# automation-v3.net
KiCad netlist of a schematic drawn in EAGLE
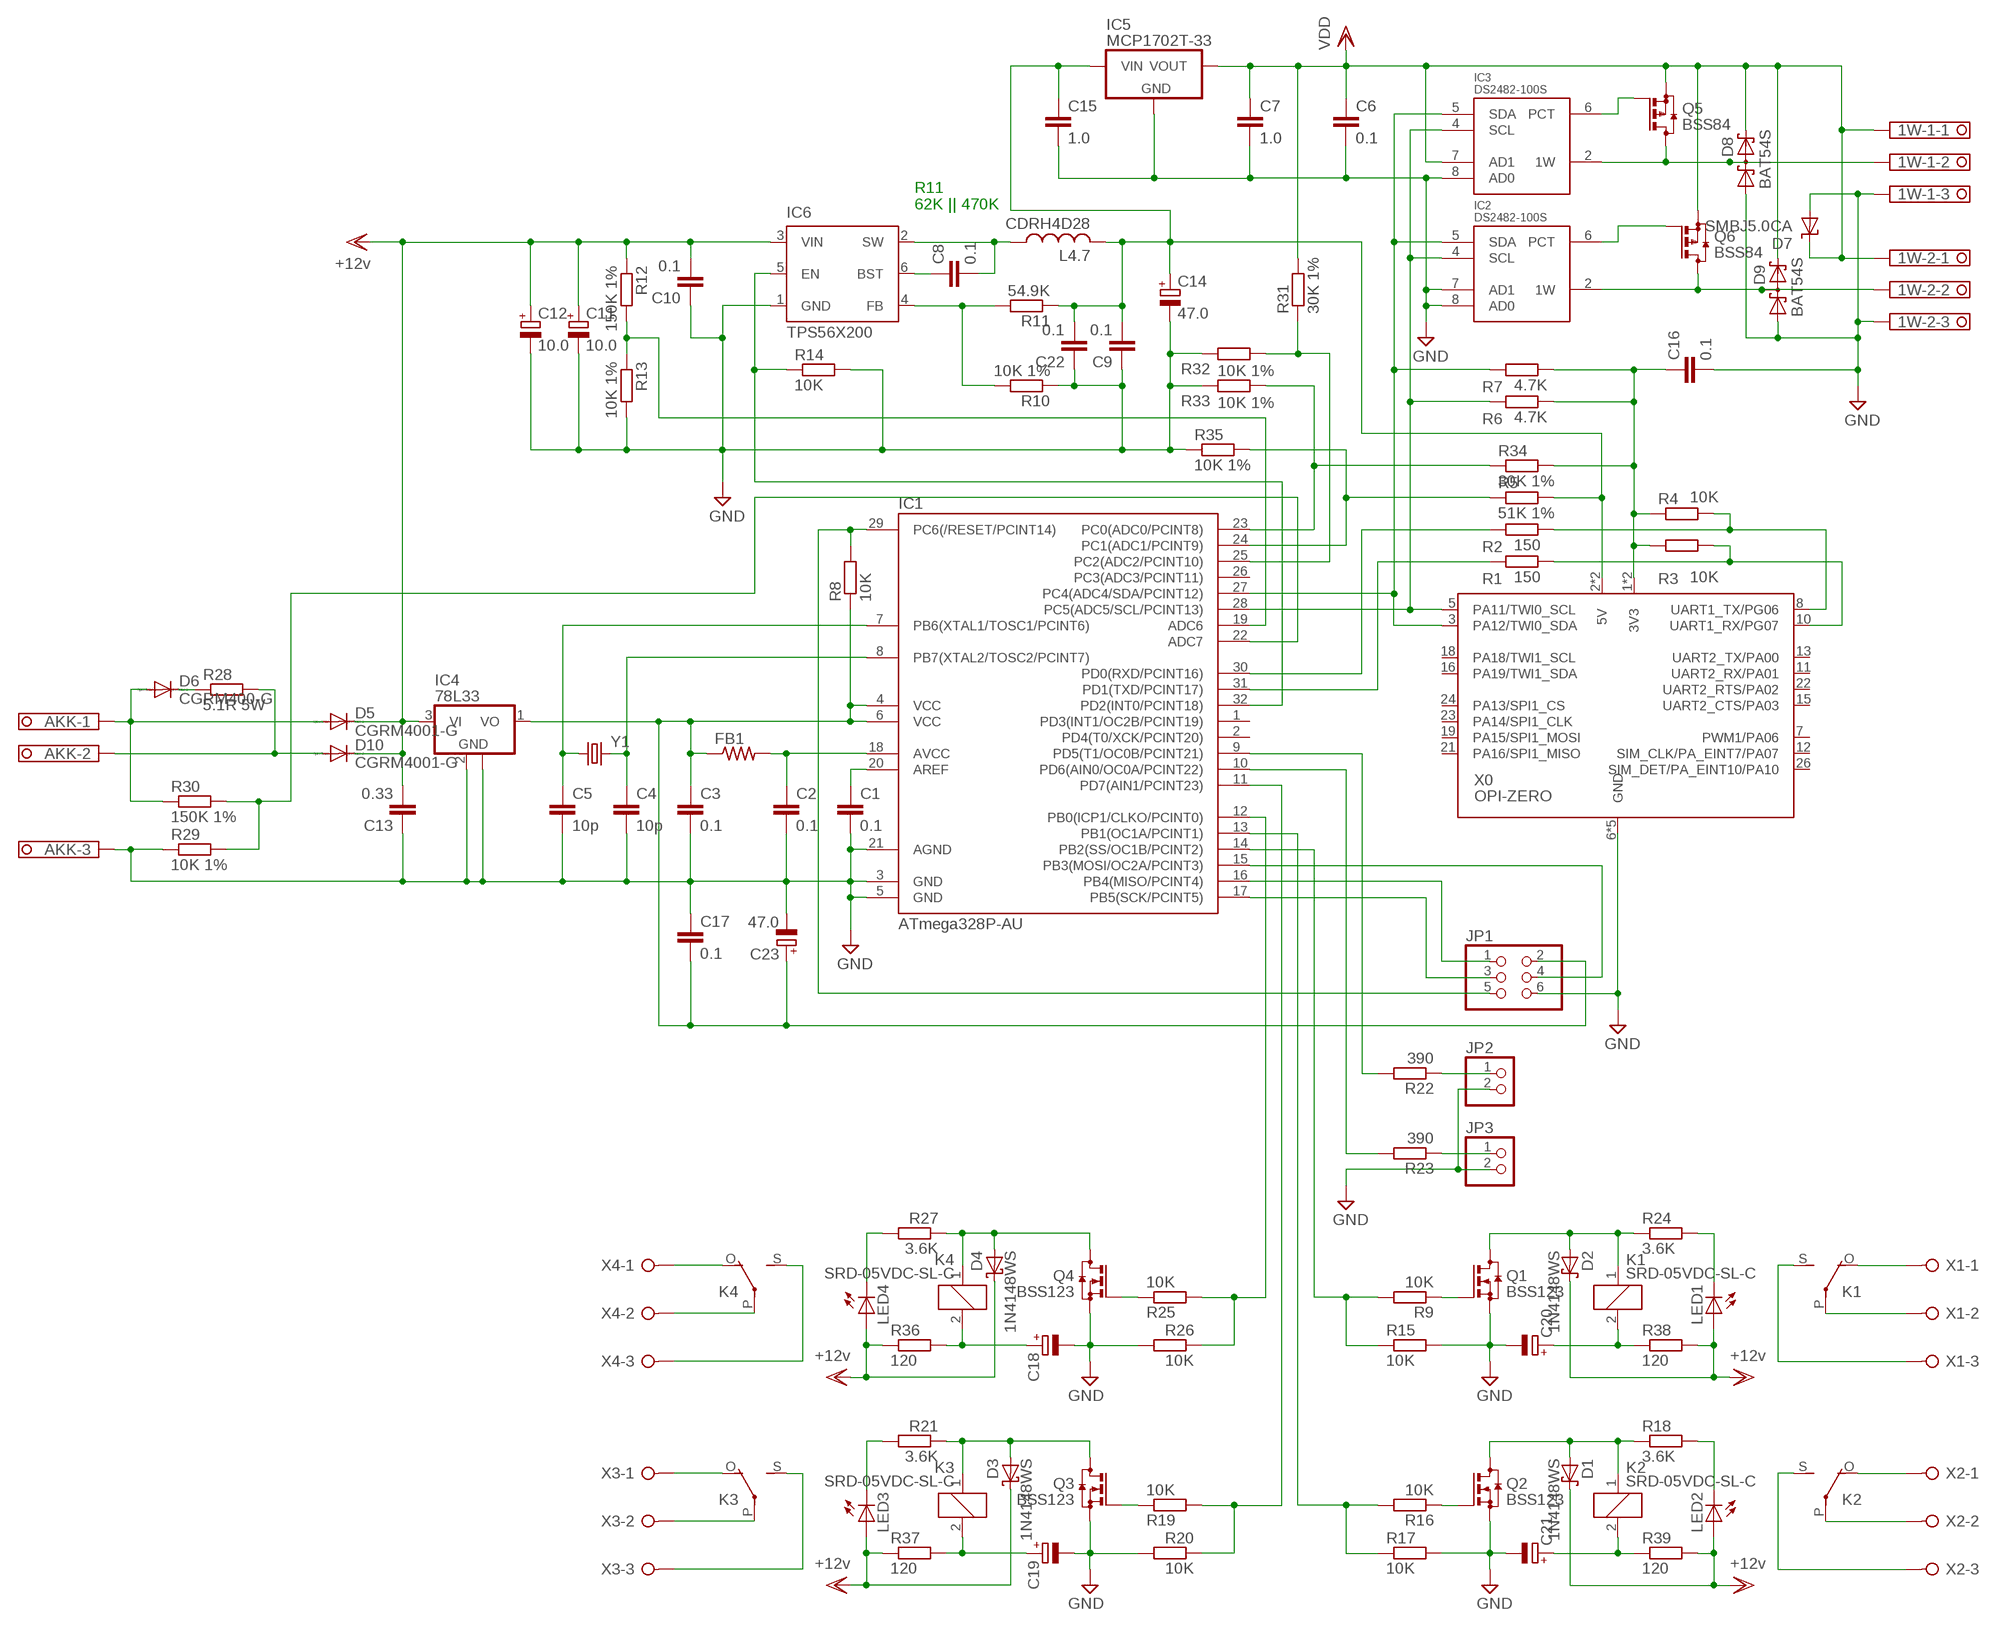
[diagram p0: schematic, sheet 1]

(export (version "E")
  (design (tool "Eeschema 10.0.6"))
  (components
    (comp (ref "1W-1")
      (value "1751251")
      (footprint "eagle-import:1751251")
      (libsource (lib "eagle-import") (part "1751251"))
    )
    (comp (ref "1W-2")
      (value "1751251")
      (footprint "eagle-import:1751251")
      (libsource (lib "eagle-import") (part "1751251"))
    )
    (comp (ref "AKK")
      (value "1751251")
      (footprint "eagle-import:1751251")
      (libsource (lib "eagle-import") (part "1751251"))
    )
    (comp (ref "C1")
      (value "0.1")
      (footprint "eagle-import:C0603")
      (libsource (lib "eagle-import") (part "C-EUC0603"))
    )
    (comp (ref "C2")
      (value "0.1")
      (footprint "eagle-import:C0603")
      (libsource (lib "eagle-import") (part "C-EUC0603"))
    )
    (comp (ref "C3")
      (value "0.1")
      (footprint "eagle-import:C0603")
      (libsource (lib "eagle-import") (part "C-EUC0603"))
    )
    (comp (ref "C4")
      (value "10p")
      (footprint "eagle-import:C0603")
      (libsource (lib "eagle-import") (part "C-EUC0603"))
    )
    (comp (ref "C5")
      (value "10p")
      (footprint "eagle-import:C0603")
      (libsource (lib "eagle-import") (part "C-EUC0603"))
    )
    (comp (ref "C6")
      (value "0.1")
      (footprint "eagle-import:C0603")
      (libsource (lib "eagle-import") (part "C-EUC0603"))
    )
    (comp (ref "C7")
      (value "1.0")
      (footprint "eagle-import:C0805")
      (libsource (lib "eagle-import") (part "C-EUC0805"))
    )
    (comp (ref "C8")
      (value "0.1")
      (footprint "eagle-import:C0805")
      (libsource (lib "eagle-import") (part "C-EUC0805"))
    )
    (comp (ref "C9")
      (value "0.1")
      (footprint "eagle-import:C0805")
      (libsource (lib "eagle-import") (part "C-EUC0805"))
    )
    (comp (ref "C10")
      (value "0.1")
      (footprint "eagle-import:C0805")
      (libsource (lib "eagle-import") (part "C-EUC0805"))
    )
    (comp (ref "C11")
      (value "10.0")
      (footprint "eagle-import:C_6032-28R")
      (libsource (lib "eagle-import") (part "CPOL-EUC/6032-28R"))
    )
    (comp (ref "C12")
      (value "10.0")
      (footprint "eagle-import:C_6032-28R")
      (libsource (lib "eagle-import") (part "CPOL-EUC/6032-28R"))
    )
    (comp (ref "C13")
      (value "0.33")
      (footprint "eagle-import:C0805")
      (libsource (lib "eagle-import") (part "C-EUC0805"))
    )
    (comp (ref "C14")
      (value "47.0")
      (footprint "eagle-import:B_3528-21R")
      (libsource (lib "eagle-import") (part "CPOL-EUB/3528-21R"))
    )
    (comp (ref "C15")
      (value "1.0")
      (footprint "eagle-import:C0805")
      (libsource (lib "eagle-import") (part "C-EUC0805"))
    )
    (comp (ref "C16")
      (value "0.1")
      (footprint "eagle-import:C0603")
      (libsource (lib "eagle-import") (part "C-EUC0603"))
    )
    (comp (ref "C17")
      (value "0.1")
      (footprint "eagle-import:C0603")
      (libsource (lib "eagle-import") (part "C-EUC0603"))
    )
    (comp (ref "C18")
      (value "CPOL-EUE5-10.5")
      (footprint "eagle-import:E5-10,5")
      (libsource (lib "eagle-import") (part "CPOL-EUE5-10.5"))
    )
    (comp (ref "C19")
      (value "CPOL-EUE5-10.5")
      (footprint "eagle-import:E5-10,5")
      (libsource (lib "eagle-import") (part "CPOL-EUE5-10.5"))
    )
    (comp (ref "C20")
      (value "CPOL-EUE5-10.5")
      (footprint "eagle-import:E5-10,5")
      (libsource (lib "eagle-import") (part "CPOL-EUE5-10.5"))
    )
    (comp (ref "C21")
      (value "CPOL-EUE5-10.5")
      (footprint "eagle-import:E5-10,5")
      (libsource (lib "eagle-import") (part "CPOL-EUE5-10.5"))
    )
    (comp (ref "C22")
      (value "0.1")
      (footprint "eagle-import:C0805")
      (libsource (lib "eagle-import") (part "C-EUC0805"))
    )
    (comp (ref "C23")
      (value "47.0")
      (footprint "eagle-import:B_3528-21R")
      (libsource (lib "eagle-import") (part "CPOL-EUB/3528-21R"))
    )
    (comp (ref "D1")
      (value "1N4148WS")
      (footprint "eagle-import:SOD323_ST")
      (libsource (lib "eagle-import") (part "BAT60J"))
    )
    (comp (ref "D2")
      (value "1N4148WS")
      (footprint "eagle-import:SOD323_ST")
      (libsource (lib "eagle-import") (part "BAT60J"))
    )
    (comp (ref "D3")
      (value "1N4148WS")
      (footprint "eagle-import:SOD323_ST")
      (libsource (lib "eagle-import") (part "BAT60J"))
    )
    (comp (ref "D4")
      (value "1N4148WS")
      (footprint "eagle-import:SOD323_ST")
      (libsource (lib "eagle-import") (part "BAT60J"))
    )
    (comp (ref "D5")
      (value "CGRM4001-G")
      (footprint "eagle-import:SOD-123_MINI-SMA")
      (libsource (lib "eagle-import") (part "CGRM400-G1"))
    )
    (comp (ref "D6")
      (value "CGRM400-G")
      (footprint "eagle-import:SOD-123_MINI-SMA")
      (libsource (lib "eagle-import") (part "CGRM400-G1"))
    )
    (comp (ref "D7")
      (value "SMBJ5.0CA")
      (footprint "eagle-import:SMBJ")
      (libsource (lib "eagle-import") (part "SUPPRESSOR-SMBJ"))
    )
    (comp (ref "D8")
      (value "BAT54S")
      (footprint "eagle-import:SOT23")
      (libsource (lib "eagle-import") (part "BAT54S"))
    )
    (comp (ref "D9")
      (value "BAT54S")
      (footprint "eagle-import:SOT23")
      (libsource (lib "eagle-import") (part "BAT54S"))
    )
    (comp (ref "D10")
      (value "CGRM4001-G")
      (footprint "eagle-import:SOD-123_MINI-SMA")
      (libsource (lib "eagle-import") (part "CGRM400-G1"))
    )
    (comp (ref "FB1")
      (value "R-US_R0805")
      (footprint "eagle-import:R0805")
      (libsource (lib "eagle-import") (part "R-US_R0805"))
    )
    (comp (ref "IC1")
      (value "ATmega328P-AU")
      (footprint "eagle-import:TQFP32-08")
      (libsource (lib "eagle-import") (part "MEGA48/88/168-AU"))
    )
    (comp (ref "IC2")
      (value "DS2482-100S")
      (footprint "eagle-import:SO08")
      (libsource (lib "eagle-import") (part "DS2482-100S"))
    )
    (comp (ref "IC3")
      (value "DS2482-100S")
      (footprint "eagle-import:SO08")
      (libsource (lib "eagle-import") (part "DS2482-100S"))
    )
    (comp (ref "IC4")
      (value "78L33")
      (footprint "eagle-import:SOT89")
      (libsource (lib "eagle-import") (part "78LF05"))
    )
    (comp (ref "IC5")
      (value "MCP1702T-33")
      (footprint "eagle-import:SOT23-3-ROTATED")
      (libsource (lib "eagle-import") (part "MCP1702SOT23"))
    )
    (comp (ref "IC6")
      (value "TPS56X200")
      (footprint "eagle-import:TSOT23-6_DDC")
      (libsource (lib "eagle-import") (part "TPS56X200"))
    )
    (comp (ref "JP1")
      (value "PINHD-2X3")
      (footprint "eagle-import:2X03")
      (libsource (lib "eagle-import") (part "PINHD-2X3"))
    )
    (comp (ref "JP2")
      (value "PINHD-1X2")
      (footprint "eagle-import:1X02")
      (libsource (lib "eagle-import") (part "PINHD-1X2"))
    )
    (comp (ref "JP3")
      (value "PINHD-1X2")
      (footprint "eagle-import:1X02")
      (libsource (lib "eagle-import") (part "PINHD-1X2"))
    )
    (comp (ref "K1")
      (value "SRD-05VDC-SL-C")
      (footprint "eagle-import:NRP18")
      (libsource (lib "eagle-import") (part "ZF112S"))
    )
    (comp (ref "K2")
      (value "SRD-05VDC-SL-C")
      (footprint "eagle-import:NRP18")
      (libsource (lib "eagle-import") (part "ZF112S"))
    )
    (comp (ref "K3")
      (value "SRD-05VDC-SL-C")
      (footprint "eagle-import:NRP18")
      (libsource (lib "eagle-import") (part "ZF112S"))
    )
    (comp (ref "K4")
      (value "SRD-05VDC-SL-C")
      (footprint "eagle-import:NRP18")
      (libsource (lib "eagle-import") (part "ZF112S"))
    )
    (comp (ref "L4.7")
      (value "CDRH4D28")
      (footprint "eagle-import:CDRH4D28")
      (libsource (lib "eagle-import") (part "CDRH4D28"))
    )
    (comp (ref "LED1")
      (value "LEDSML0805")
      (footprint "eagle-import:SML0805")
      (libsource (lib "eagle-import") (part "LEDSML0805"))
    )
    (comp (ref "LED2")
      (value "LEDSML0805")
      (footprint "eagle-import:SML0805")
      (libsource (lib "eagle-import") (part "LEDSML0805"))
    )
    (comp (ref "LED3")
      (value "LEDSML0805")
      (footprint "eagle-import:SML0805")
      (libsource (lib "eagle-import") (part "LEDSML0805"))
    )
    (comp (ref "LED4")
      (value "LEDSML0805")
      (footprint "eagle-import:SML0805")
      (libsource (lib "eagle-import") (part "LEDSML0805"))
    )
    (comp (ref "Q1")
      (value "BSS123")
      (footprint "eagle-import:SOT23")
      (libsource (lib "eagle-import") (part "BSS123"))
    )
    (comp (ref "Q2")
      (value "BSS123")
      (footprint "eagle-import:SOT23")
      (libsource (lib "eagle-import") (part "BSS123"))
    )
    (comp (ref "Q3")
      (value "BSS123")
      (footprint "eagle-import:SOT23")
      (libsource (lib "eagle-import") (part "BSS123"))
    )
    (comp (ref "Q4")
      (value "BSS123")
      (footprint "eagle-import:SOT23")
      (libsource (lib "eagle-import") (part "BSS123"))
    )
    (comp (ref "Q5")
      (value "BSS84")
      (footprint "eagle-import:SOT23")
      (libsource (lib "eagle-import") (part "BSS84"))
    )
    (comp (ref "Q6")
      (value "BSS84")
      (footprint "eagle-import:SOT23")
      (libsource (lib "eagle-import") (part "BSS84"))
    )
    (comp (ref "R1")
      (value "150")
      (footprint "eagle-import:R0603")
      (libsource (lib "eagle-import") (part "R-EU_R0603"))
    )
    (comp (ref "R2")
      (value "150")
      (footprint "eagle-import:R0603")
      (libsource (lib "eagle-import") (part "R-EU_R0603"))
    )
    (comp (ref "R3")
      (value "10K")
      (footprint "eagle-import:R0603")
      (libsource (lib "eagle-import") (part "R-EU_R0603"))
    )
    (comp (ref "R4")
      (value "10K")
      (footprint "eagle-import:R0603")
      (libsource (lib "eagle-import") (part "R-EU_R0603"))
    )
    (comp (ref "R5")
      (value "51K 1%")
      (footprint "eagle-import:R0603")
      (libsource (lib "eagle-import") (part "R-EU_R0603"))
    )
    (comp (ref "R6")
      (value "4.7K")
      (footprint "eagle-import:R0603")
      (libsource (lib "eagle-import") (part "R-EU_R0603"))
    )
    (comp (ref "R7")
      (value "4.7K")
      (footprint "eagle-import:R0603")
      (libsource (lib "eagle-import") (part "R-EU_R0603"))
    )
    (comp (ref "R8")
      (value "10K")
      (footprint "eagle-import:R0603")
      (libsource (lib "eagle-import") (part "R-EU_R0603"))
    )
    (comp (ref "R9")
      (value "10K")
      (footprint "eagle-import:R0603")
      (libsource (lib "eagle-import") (part "R-EU_R0603"))
    )
    (comp (ref "R10")
      (value "10K 1%")
      (footprint "eagle-import:R0603")
      (libsource (lib "eagle-import") (part "R-EU_R0603"))
    )
    (comp (ref "R11")
      (value "54.9K")
      (footprint "eagle-import:R0603")
      (libsource (lib "eagle-import") (part "R-EU_R0603"))
    )
    (comp (ref "R12")
      (value "150K 1%")
      (footprint "eagle-import:R0603")
      (libsource (lib "eagle-import") (part "R-EU_R0603"))
    )
    (comp (ref "R13")
      (value "10K 1%")
      (footprint "eagle-import:R0603")
      (libsource (lib "eagle-import") (part "R-EU_R0603"))
    )
    (comp (ref "R14")
      (value "10K")
      (footprint "eagle-import:R0603")
      (libsource (lib "eagle-import") (part "R-EU_R0603"))
    )
    (comp (ref "R15")
      (value "10K")
      (footprint "eagle-import:R0603")
      (libsource (lib "eagle-import") (part "R-EU_R0603"))
    )
    (comp (ref "R16")
      (value "10K")
      (footprint "eagle-import:R0603")
      (libsource (lib "eagle-import") (part "R-EU_R0603"))
    )
    (comp (ref "R17")
      (value "10K")
      (footprint "eagle-import:R0603")
      (libsource (lib "eagle-import") (part "R-EU_R0603"))
    )
    (comp (ref "R18")
      (value "3.6K")
      (footprint "eagle-import:R0603")
      (libsource (lib "eagle-import") (part "R-EU_R0603"))
    )
    (comp (ref "R19")
      (value "10K")
      (footprint "eagle-import:R0603")
      (libsource (lib "eagle-import") (part "R-EU_R0603"))
    )
    (comp (ref "R20")
      (value "10K")
      (footprint "eagle-import:R0603")
      (libsource (lib "eagle-import") (part "R-EU_R0603"))
    )
    (comp (ref "R21")
      (value "3.6K")
      (footprint "eagle-import:R0603")
      (libsource (lib "eagle-import") (part "R-EU_R0603"))
    )
    (comp (ref "R22")
      (value "390")
      (footprint "eagle-import:R0603")
      (libsource (lib "eagle-import") (part "R-EU_R0603"))
    )
    (comp (ref "R23")
      (value "390")
      (footprint "eagle-import:R0603")
      (libsource (lib "eagle-import") (part "R-EU_R0603"))
    )
    (comp (ref "R24")
      (value "3.6K")
      (footprint "eagle-import:R0603")
      (libsource (lib "eagle-import") (part "R-EU_R0603"))
    )
    (comp (ref "R25")
      (value "10K")
      (footprint "eagle-import:R0603")
      (libsource (lib "eagle-import") (part "R-EU_R0603"))
    )
    (comp (ref "R26")
      (value "10K")
      (footprint "eagle-import:R0603")
      (libsource (lib "eagle-import") (part "R-EU_R0603"))
    )
    (comp (ref "R27")
      (value "3.6K")
      (footprint "eagle-import:R0603")
      (libsource (lib "eagle-import") (part "R-EU_R0603"))
    )
    (comp (ref "R28")
      (value "5.1R 5W")
      (footprint "eagle-import:VTA55")
      (libsource (lib "eagle-import") (part "R-EU_VTA55"))
    )
    (comp (ref "R29")
      (value "10K 1%")
      (footprint "eagle-import:R0603")
      (libsource (lib "eagle-import") (part "R-EU_R0603"))
    )
    (comp (ref "R30")
      (value "150K 1%")
      (footprint "eagle-import:R0603")
      (libsource (lib "eagle-import") (part "R-EU_R0603"))
    )
    (comp (ref "R31")
      (value "30K 1%")
      (footprint "eagle-import:R0603")
      (libsource (lib "eagle-import") (part "R-EU_R0603"))
    )
    (comp (ref "R32")
      (value "10K 1%")
      (footprint "eagle-import:R0603")
      (libsource (lib "eagle-import") (part "R-EU_R0603"))
    )
    (comp (ref "R33")
      (value "10K 1%")
      (footprint "eagle-import:R0603")
      (libsource (lib "eagle-import") (part "R-EU_R0603"))
    )
    (comp (ref "R34")
      (value "30K 1%")
      (footprint "eagle-import:R0603")
      (libsource (lib "eagle-import") (part "R-EU_R0603"))
    )
    (comp (ref "R35")
      (value "10K 1%")
      (footprint "eagle-import:R0603")
      (libsource (lib "eagle-import") (part "R-EU_R0603"))
    )
    (comp (ref "R36")
      (value "120")
      (footprint "eagle-import:M1206")
      (libsource (lib "eagle-import") (part "R-EU_M1206"))
    )
    (comp (ref "R37")
      (value "120")
      (footprint "eagle-import:M1206")
      (libsource (lib "eagle-import") (part "R-EU_M1206"))
    )
    (comp (ref "R38")
      (value "120")
      (footprint "eagle-import:M1206")
      (libsource (lib "eagle-import") (part "R-EU_M1206"))
    )
    (comp (ref "R39")
      (value "120")
      (footprint "eagle-import:M1206")
      (libsource (lib "eagle-import") (part "R-EU_M1206"))
    )
    (comp (ref "X0")
      (value "OPI-ZERO")
      (footprint "eagle-import:OPI0")
      (libsource (lib "eagle-import") (part "OPI-ZERO"))
    )
    (comp (ref "X1")
      (value "W237-03P")
      (footprint "eagle-import:W237-133")
      (libsource (lib "eagle-import") (part "W237-03P"))
    )
    (comp (ref "X2")
      (value "W237-03P")
      (footprint "eagle-import:W237-133")
      (libsource (lib "eagle-import") (part "W237-03P"))
    )
    (comp (ref "X3")
      (value "W237-03P")
      (footprint "eagle-import:W237-133")
      (libsource (lib "eagle-import") (part "W237-03P"))
    )
    (comp (ref "X4")
      (value "W237-03P")
      (footprint "eagle-import:W237-133")
      (libsource (lib "eagle-import") (part "W237-03P"))
    )
    (comp (ref "Y1")
      (value "CRYSTALHC49US")
      (footprint "eagle-import:HC49US")
      (libsource (lib "eagle-import") (part "CRYSTALHC49US"))
    )
  )
  (nets
    (net (code "1") (name "+12v") (class "Default")
      (node (ref "C10") (pin "2") (pinfunction "2_2") (pintype "passive"))
      (node (ref "C11") (pin "+") (pinfunction "+_+") (pintype "passive"))
      (node (ref "C12") (pin "+") (pinfunction "+_+") (pintype "passive"))
      (node (ref "C13") (pin "2") (pinfunction "2_2") (pintype "passive"))
      (node (ref "D1") (pin "C") (pinfunction "C_C") (pintype "passive"))
      (node (ref "D10") (pin "C") (pinfunction "C_C") (pintype "passive"))
      (node (ref "D2") (pin "C") (pinfunction "C_C") (pintype "passive"))
      (node (ref "D3") (pin "C") (pinfunction "C_C") (pintype "passive"))
      (node (ref "D4") (pin "C") (pinfunction "C_C") (pintype "passive"))
      (node (ref "D5") (pin "C") (pinfunction "C_C") (pintype "passive"))
      (node (ref "IC4") (pin "3") (pinfunction "VI_3") (pintype "input"))
      (node (ref "IC6") (pin "3") (pinfunction "VIN_3") (pintype "input"))
      (node (ref "LED1") (pin "A") (pinfunction "A_A") (pintype "passive"))
      (node (ref "LED2") (pin "A") (pinfunction "A_A") (pintype "passive"))
      (node (ref "LED3") (pin "A") (pinfunction "A_A") (pintype "passive"))
      (node (ref "LED4") (pin "A") (pinfunction "A_A") (pintype "passive"))
      (node (ref "R12") (pin "1") (pinfunction "1_1") (pintype "passive"))
      (node (ref "R36") (pin "1") (pinfunction "1_1") (pintype "passive"))
      (node (ref "R37") (pin "1") (pinfunction "1_1") (pintype "passive"))
      (node (ref "R38") (pin "2") (pinfunction "2_2") (pintype "passive"))
      (node (ref "R39") (pin "2") (pinfunction "2_2") (pintype "passive"))
    )
    (net (code "2") (name "GND") (class "Default")
      (node (ref "1W-1") (pin "3") (pinfunction "K_3") (pintype "passive"))
      (node (ref "1W-2") (pin "3") (pinfunction "K_3") (pintype "passive"))
      (node (ref "AKK") (pin "3") (pinfunction "K_3") (pintype "passive"))
      (node (ref "C1") (pin "2") (pinfunction "2_2") (pintype "passive"))
      (node (ref "C10") (pin "1") (pinfunction "1_1") (pintype "passive"))
      (node (ref "C11") (pin "-") (pinfunction "-_-") (pintype "passive"))
      (node (ref "C12") (pin "-") (pinfunction "-_-") (pintype "passive"))
      (node (ref "C13") (pin "1") (pinfunction "1_1") (pintype "passive"))
      (node (ref "C14") (pin "-") (pinfunction "-_-") (pintype "passive"))
      (node (ref "C15") (pin "2") (pinfunction "2_2") (pintype "passive"))
      (node (ref "C16") (pin "2") (pinfunction "2_2") (pintype "passive"))
      (node (ref "C17") (pin "1") (pinfunction "1_1") (pintype "passive"))
      (node (ref "C18") (pin "-") (pinfunction "-_-") (pintype "passive"))
      (node (ref "C19") (pin "-") (pinfunction "-_-") (pintype "passive"))
      (node (ref "C2") (pin "2") (pinfunction "2_2") (pintype "passive"))
      (node (ref "C20") (pin "-") (pinfunction "-_-") (pintype "passive"))
      (node (ref "C21") (pin "-") (pinfunction "-_-") (pintype "passive"))
      (node (ref "C22") (pin "1") (pinfunction "1_1") (pintype "passive"))
      (node (ref "C23") (pin "-") (pinfunction "-_-") (pintype "passive"))
      (node (ref "C3") (pin "2") (pinfunction "2_2") (pintype "passive"))
      (node (ref "C4") (pin "2") (pinfunction "2_2") (pintype "passive"))
      (node (ref "C5") (pin "2") (pinfunction "2_2") (pintype "passive"))
      (node (ref "C6") (pin "2") (pinfunction "2_2") (pintype "passive"))
      (node (ref "C7") (pin "2") (pinfunction "2_2") (pintype "passive"))
      (node (ref "C9") (pin "1") (pinfunction "1_1") (pintype "passive"))
      (node (ref "D7") (pin "A") (pinfunction "A_A") (pintype "passive"))
      (node (ref "D8") (pin "1") (pinfunction "A1_1") (pintype "passive"))
      (node (ref "D9") (pin "1") (pinfunction "A1_1") (pintype "passive"))
      (node (ref "IC1") (pin "21") (pinfunction "AGND_21") (pintype "power_in"))
      (node (ref "IC1") (pin "3") (pinfunction "GND_3") (pintype "power_in"))
      (node (ref "IC1") (pin "5") (pinfunction "GND_5") (pintype "power_in"))
      (node (ref "IC2") (pin "7") (pinfunction "AD1_7") (pintype "input"))
      (node (ref "IC2") (pin "8") (pinfunction "AD0_8") (pintype "input"))
      (node (ref "IC3") (pin "8") (pinfunction "AD0_8") (pintype "input"))
      (node (ref "IC4") (pin "2") (pinfunction "GND_2") (pintype "passive"))
      (node (ref "IC4") (pin "2@1") (pinfunction "GND_2@1") (pintype "passive"))
      (node (ref "IC5") (pin "1") (pinfunction "GND_1") (pintype "passive"))
      (node (ref "IC6") (pin "1") (pinfunction "GND_1") (pintype "power_in"))
      (node (ref "JP1") (pin "6") (pinfunction "6_6") (pintype "passive"))
      (node (ref "JP2") (pin "2") (pinfunction "2_2") (pintype "passive"))
      (node (ref "JP3") (pin "2") (pinfunction "2_2") (pintype "passive"))
      (node (ref "Q1") (pin "2") (pinfunction "S_2") (pintype "passive"))
      (node (ref "Q2") (pin "2") (pinfunction "S_2") (pintype "passive"))
      (node (ref "Q3") (pin "2") (pinfunction "S_2") (pintype "passive"))
      (node (ref "Q4") (pin "2") (pinfunction "S_2") (pintype "passive"))
      (node (ref "R10") (pin "1") (pinfunction "1_1") (pintype "passive"))
      (node (ref "R13") (pin "2") (pinfunction "2_2") (pintype "passive"))
      (node (ref "R14") (pin "2") (pinfunction "2_2") (pintype "passive"))
      (node (ref "R15") (pin "2") (pinfunction "2_2") (pintype "passive"))
      (node (ref "R17") (pin "2") (pinfunction "2_2") (pintype "passive"))
      (node (ref "R20") (pin "2") (pinfunction "2_2") (pintype "passive"))
      (node (ref "R26") (pin "2") (pinfunction "2_2") (pintype "passive"))
      (node (ref "R29") (pin "1") (pinfunction "1_1") (pintype "passive"))
      (node (ref "R32") (pin "2") (pinfunction "2_2") (pintype "passive"))
      (node (ref "R33") (pin "2") (pinfunction "2_2") (pintype "passive"))
      (node (ref "R35") (pin "1") (pinfunction "1_1") (pintype "passive"))
      (node (ref "X0") (pin "14") (pinfunction "GND_14") (pintype "power_in"))
      (node (ref "X0") (pin "20") (pinfunction "GND_20") (pintype "power_in"))
      (node (ref "X0") (pin "25") (pinfunction "GND_25") (pintype "power_in"))
      (node (ref "X0") (pin "6") (pinfunction "GND_6") (pintype "power_in"))
      (node (ref "X0") (pin "9") (pinfunction "GND_9") (pintype "power_in"))
    )
    (net (code "3") (name "Net-(1W-1B-K)") (class "Default")
      (node (ref "1W-1") (pin "2") (pinfunction "K_2") (pintype "passive"))
      (node (ref "D8") (pin "3") (pinfunction "C1A2_3") (pintype "passive"))
      (node (ref "IC3") (pin "2") (pinfunction "1W_2") (pintype "open_collector"))
      (node (ref "Q5") (pin "3") (pinfunction "D_3") (pintype "passive"))
    )
    (net (code "4") (name "Net-(1W-2B-K)") (class "Default")
      (node (ref "1W-2") (pin "2") (pinfunction "K_2") (pintype "passive"))
      (node (ref "D9") (pin "3") (pinfunction "C1A2_3") (pintype "passive"))
      (node (ref "IC2") (pin "2") (pinfunction "1W_2") (pintype "open_collector"))
      (node (ref "Q6") (pin "3") (pinfunction "D_3") (pintype "passive"))
    )
    (net (code "5") (name "Net-(AKKA-K)") (class "Default")
      (node (ref "AKK") (pin "1") (pinfunction "K_1") (pintype "passive"))
      (node (ref "D5") (pin "A") (pinfunction "A_A") (pintype "passive"))
      (node (ref "D6") (pin "A") (pinfunction "A_A") (pintype "passive"))
      (node (ref "R30") (pin "1") (pinfunction "1_1") (pintype "passive"))
    )
    (net (code "6") (name "Net-(AKKB-K)") (class "Default")
      (node (ref "AKK") (pin "2") (pinfunction "K_2") (pintype "passive"))
      (node (ref "D10") (pin "A") (pinfunction "A_A") (pintype "passive"))
      (node (ref "R28") (pin "2") (pinfunction "2_2") (pintype "passive"))
    )
    (net (code "7") (name "Net-(C16-Pad1)") (class "Default")
      (node (ref "C16") (pin "1") (pinfunction "1_1") (pintype "passive"))
      (node (ref "R3") (pin "1") (pinfunction "1_1") (pintype "passive"))
      (node (ref "R34") (pin "2") (pinfunction "2_2") (pintype "passive"))
      (node (ref "R4") (pin "1") (pinfunction "1_1") (pintype "passive"))
      (node (ref "R6") (pin "2") (pinfunction "2_2") (pintype "passive"))
      (node (ref "R7") (pin "2") (pinfunction "2_2") (pintype "passive"))
      (node (ref "X0") (pin "1") (pinfunction "3V3_1") (pintype "power_in"))
      (node (ref "X0") (pin "17") (pinfunction "3V3_17") (pintype "power_in"))
    )
    (net (code "8") (name "Net-(C18-Pad+)") (class "Default")
      (node (ref "C18") (pin "+") (pinfunction "+_+") (pintype "passive"))
      (node (ref "K4") (pin "2") (pinfunction "2_2") (pintype "passive"))
      (node (ref "R36") (pin "2") (pinfunction "2_2") (pintype "passive"))
    )
    (net (code "9") (name "Net-(C19-Pad+)") (class "Default")
      (node (ref "C19") (pin "+") (pinfunction "+_+") (pintype "passive"))
      (node (ref "K3") (pin "2") (pinfunction "2_2") (pintype "passive"))
      (node (ref "R37") (pin "2") (pinfunction "2_2") (pintype "passive"))
    )
    (net (code "10") (name "Net-(C20-Pad+)") (class "Default")
      (node (ref "C20") (pin "+") (pinfunction "+_+") (pintype "passive"))
      (node (ref "K1") (pin "2") (pinfunction "2_2") (pintype "passive"))
      (node (ref "R38") (pin "1") (pinfunction "1_1") (pintype "passive"))
    )
    (net (code "11") (name "Net-(C21-Pad+)") (class "Default")
      (node (ref "C21") (pin "+") (pinfunction "+_+") (pintype "passive"))
      (node (ref "K2") (pin "2") (pinfunction "2_2") (pintype "passive"))
      (node (ref "R39") (pin "1") (pinfunction "1_1") (pintype "passive"))
    )
    (net (code "12") (name "Net-(D6-PadC)") (class "Default")
      (node (ref "D6") (pin "C") (pinfunction "C_C") (pintype "passive"))
      (node (ref "R28") (pin "1") (pinfunction "1_1") (pintype "passive"))
    )
    (net (code "13") (name "Net-(IC1-ADC6)") (class "Default")
      (node (ref "IC1") (pin "19") (pinfunction "ADC6_19") (pintype "passive"))
      (node (ref "R12") (pin "2") (pinfunction "2_2") (pintype "passive"))
      (node (ref "R13") (pin "1") (pinfunction "1_1") (pintype "passive"))
    )
    (net (code "14") (name "Net-(IC1-ADC7)") (class "Default")
      (node (ref "IC1") (pin "22") (pinfunction "ADC7_22") (pintype "passive"))
      (node (ref "R29") (pin "2") (pinfunction "2_2") (pintype "passive"))
      (node (ref "R30") (pin "2") (pinfunction "2_2") (pintype "passive"))
    )
    (net (code "15") (name "Net-(IC1-AREF)") (class "Default")
      (node (ref "C1") (pin "1") (pinfunction "1_1") (pintype "passive"))
      (node (ref "IC1") (pin "20") (pinfunction "AREF_20") (pintype "passive"))
    )
    (net (code "16") (name "Net-(IC1-AVCC)") (class "Default")
      (node (ref "C2") (pin "1") (pinfunction "1_1") (pintype "passive"))
      (node (ref "FB1") (pin "2") (pinfunction "2_2") (pintype "passive"))
      (node (ref "IC1") (pin "18") (pinfunction "AVCC_18") (pintype "passive"))
    )
    (net (code "17") (name "Net-(IC1-PB0(ICP1{slash}CLKO{slash}PCINT0))") (class "Default")
      (node (ref "IC1") (pin "12") (pinfunction "PB0(ICP1/CLKO/PCINT0)_12") (pintype "bidirectional"))
      (node (ref "R25") (pin "2") (pinfunction "2_2") (pintype "passive"))
      (node (ref "R26") (pin "1") (pinfunction "1_1") (pintype "passive"))
    )
    (net (code "18") (name "Net-(IC1-PB1(OC1A{slash}PCINT1))") (class "Default")
      (node (ref "IC1") (pin "13") (pinfunction "PB1(OC1A/PCINT1)_13") (pintype "bidirectional"))
      (node (ref "R16") (pin "2") (pinfunction "2_2") (pintype "passive"))
      (node (ref "R17") (pin "1") (pinfunction "1_1") (pintype "passive"))
    )
    (net (code "19") (name "Net-(IC1-PB2(SS{slash}OC1B{slash}PCINT2))") (class "Default")
      (node (ref "IC1") (pin "14") (pinfunction "PB2(SS/OC1B/PCINT2)_14") (pintype "bidirectional"))
      (node (ref "R15") (pin "1") (pinfunction "1_1") (pintype "passive"))
      (node (ref "R9") (pin "2") (pinfunction "2_2") (pintype "passive"))
    )
    (net (code "20") (name "Net-(IC1-PB3(MOSI{slash}OC2A{slash}PCINT3))") (class "Default")
      (node (ref "IC1") (pin "15") (pinfunction "PB3(MOSI/OC2A/PCINT3)_15") (pintype "bidirectional"))
      (node (ref "JP1") (pin "4") (pinfunction "4_4") (pintype "passive"))
    )
    (net (code "21") (name "Net-(IC1-PB4(MISO{slash}PCINT4))") (class "Default")
      (node (ref "IC1") (pin "16") (pinfunction "PB4(MISO/PCINT4)_16") (pintype "bidirectional"))
      (node (ref "JP1") (pin "1") (pinfunction "1_1") (pintype "passive"))
    )
    (net (code "22") (name "Net-(IC1-PB5(SCK{slash}PCINT5))") (class "Default")
      (node (ref "IC1") (pin "17") (pinfunction "PB5(SCK/PCINT5)_17") (pintype "bidirectional"))
      (node (ref "JP1") (pin "3") (pinfunction "3_3") (pintype "passive"))
    )
    (net (code "23") (name "Net-(IC1-PB6(XTAL1{slash}TOSC1{slash}PCINT6))") (class "Default")
      (node (ref "C5") (pin "1") (pinfunction "1_1") (pintype "passive"))
      (node (ref "IC1") (pin "7") (pinfunction "PB6(XTAL1/TOSC1/PCINT6)_7") (pintype "bidirectional"))
      (node (ref "Y1") (pin "1") (pinfunction "1_1") (pintype "passive"))
    )
    (net (code "24") (name "Net-(IC1-PB7(XTAL2{slash}TOSC2{slash}PCINT7))") (class "Default")
      (node (ref "C4") (pin "1") (pinfunction "1_1") (pintype "passive"))
      (node (ref "IC1") (pin "8") (pinfunction "PB7(XTAL2/TOSC2/PCINT7)_8") (pintype "bidirectional"))
      (node (ref "Y1") (pin "2") (pinfunction "2_2") (pintype "passive"))
    )
    (net (code "25") (name "Net-(IC1-PC0(ADC0{slash}PCINT8))") (class "Default")
      (node (ref "IC1") (pin "23") (pinfunction "PC0(ADC0/PCINT8)_23") (pintype "bidirectional"))
      (node (ref "R33") (pin "1") (pinfunction "1_1") (pintype "passive"))
      (node (ref "R34") (pin "1") (pinfunction "1_1") (pintype "passive"))
    )
    (net (code "26") (name "Net-(IC1-PC1(ADC1{slash}PCINT9))") (class "Default")
      (node (ref "IC1") (pin "24") (pinfunction "PC1(ADC1/PCINT9)_24") (pintype "bidirectional"))
      (node (ref "R35") (pin "2") (pinfunction "2_2") (pintype "passive"))
      (node (ref "R5") (pin "1") (pinfunction "1_1") (pintype "passive"))
    )
    (net (code "27") (name "Net-(IC1-PC2(ADC2{slash}PCINT10))") (class "Default")
      (node (ref "IC1") (pin "25") (pinfunction "PC2(ADC2/PCINT10)_25") (pintype "bidirectional"))
      (node (ref "R31") (pin "1") (pinfunction "1_1") (pintype "passive"))
      (node (ref "R32") (pin "1") (pinfunction "1_1") (pintype "passive"))
    )
    (net (code "28") (name "Net-(IC1-PC4(ADC4{slash}SDA{slash}PCINT12))") (class "Default")
      (node (ref "IC1") (pin "27") (pinfunction "PC4(ADC4/SDA/PCINT12)_27") (pintype "bidirectional"))
      (node (ref "IC2") (pin "5") (pinfunction "SDA_5") (pintype "bidirectional"))
      (node (ref "IC3") (pin "5") (pinfunction "SDA_5") (pintype "bidirectional"))
      (node (ref "R7") (pin "1") (pinfunction "1_1") (pintype "passive"))
      (node (ref "X0") (pin "3") (pinfunction "PA12/TWI0_SDA_3") (pintype "bidirectional"))
    )
    (net (code "29") (name "Net-(IC1-PC5(ADC5{slash}SCL{slash}PCINT13))") (class "Default")
      (node (ref "IC1") (pin "28") (pinfunction "PC5(ADC5/SCL/PCINT13)_28") (pintype "bidirectional"))
      (node (ref "IC2") (pin "4") (pinfunction "SCL_4") (pintype "input"))
      (node (ref "IC3") (pin "4") (pinfunction "SCL_4") (pintype "input"))
      (node (ref "R6") (pin "1") (pinfunction "1_1") (pintype "passive"))
      (node (ref "X0") (pin "5") (pinfunction "PA11/TWI0_SCL_5") (pintype "bidirectional"))
    )
    (net (code "30") (name "Net-(IC1-PC6({slash}RESET{slash}PCINT14))") (class "Default")
      (node (ref "IC1") (pin "29") (pinfunction "PC6(/RESET/PCINT14)_29") (pintype "bidirectional"))
      (node (ref "JP1") (pin "5") (pinfunction "5_5") (pintype "passive"))
      (node (ref "R8") (pin "2") (pinfunction "2_2") (pintype "passive"))
    )
    (net (code "31") (name "Net-(IC1-PD0(RXD{slash}PCINT16))") (class "Default")
      (node (ref "IC1") (pin "30") (pinfunction "PD0(RXD/PCINT16)_30") (pintype "bidirectional"))
      (node (ref "R2") (pin "1") (pinfunction "1_1") (pintype "passive"))
    )
    (net (code "32") (name "Net-(IC1-PD1(TXD{slash}PCINT17))") (class "Default")
      (node (ref "IC1") (pin "31") (pinfunction "PD1(TXD/PCINT17)_31") (pintype "bidirectional"))
      (node (ref "R1") (pin "1") (pinfunction "1_1") (pintype "passive"))
    )
    (net (code "33") (name "Net-(IC1-PD2(INT0{slash}PCINT18))") (class "Default")
      (node (ref "IC1") (pin "32") (pinfunction "PD2(INT0/PCINT18)_32") (pintype "bidirectional"))
      (node (ref "IC6") (pin "5") (pinfunction "EN_5") (pintype "input"))
      (node (ref "R14") (pin "1") (pinfunction "1_1") (pintype "passive"))
    )
    (net (code "34") (name "Net-(IC1-PD5(T1{slash}OC0B{slash}PCINT21))") (class "Default")
      (node (ref "IC1") (pin "9") (pinfunction "PD5(T1/OC0B/PCINT21)_9") (pintype "bidirectional"))
      (node (ref "R22") (pin "2") (pinfunction "2_2") (pintype "passive"))
    )
    (net (code "35") (name "Net-(IC1-PD6(AIN0{slash}OC0A{slash}PCINT22))") (class "Default")
      (node (ref "IC1") (pin "10") (pinfunction "PD6(AIN0/OC0A/PCINT22)_10") (pintype "bidirectional"))
      (node (ref "R23") (pin "2") (pinfunction "2_2") (pintype "passive"))
    )
    (net (code "36") (name "Net-(IC1-PD7(AIN1{slash}PCINT23))") (class "Default")
      (node (ref "IC1") (pin "11") (pinfunction "PD7(AIN1/PCINT23)_11") (pintype "bidirectional"))
      (node (ref "R19") (pin "2") (pinfunction "2_2") (pintype "passive"))
      (node (ref "R20") (pin "1") (pinfunction "1_1") (pintype "passive"))
    )
    (net (code "37") (name "Net-(IC2A-PCT)") (class "Default")
      (node (ref "IC2") (pin "6") (pinfunction "PCT_6") (pintype "output"))
      (node (ref "Q6") (pin "1") (pinfunction "G_1") (pintype "passive"))
    )
    (net (code "38") (name "Net-(IC3A-PCT)") (class "Default")
      (node (ref "IC3") (pin "6") (pinfunction "PCT_6") (pintype "output"))
      (node (ref "Q5") (pin "1") (pinfunction "G_1") (pintype "passive"))
    )
    (net (code "39") (name "Net-(IC4-VO)") (class "Default")
      (node (ref "C17") (pin "2") (pinfunction "2_2") (pintype "passive"))
      (node (ref "C23") (pin "+") (pinfunction "+_+") (pintype "passive"))
      (node (ref "C3") (pin "1") (pinfunction "1_1") (pintype "passive"))
      (node (ref "FB1") (pin "1") (pinfunction "1_1") (pintype "passive"))
      (node (ref "IC1") (pin "4") (pinfunction "VCC_4") (pintype "power_in"))
      (node (ref "IC1") (pin "6") (pinfunction "VCC_6") (pintype "power_in"))
      (node (ref "IC4") (pin "1") (pinfunction "VO_1") (pintype "passive"))
      (node (ref "JP1") (pin "2") (pinfunction "2_2") (pintype "passive"))
      (node (ref "R8") (pin "1") (pinfunction "1_1") (pintype "passive"))
    )
    (net (code "40") (name "Net-(IC5-VIN)") (class "Default")
      (node (ref "C14") (pin "+") (pinfunction "+_+") (pintype "passive"))
      (node (ref "C15") (pin "1") (pinfunction "1_1") (pintype "passive"))
      (node (ref "C22") (pin "2") (pinfunction "2_2") (pintype "passive"))
      (node (ref "C9") (pin "2") (pinfunction "2_2") (pintype "passive"))
      (node (ref "IC5") (pin "3") (pinfunction "VIN_3") (pintype "input"))
      (node (ref "L4.7") (pin "P$2") (pinfunction "2_P$2") (pintype "passive"))
      (node (ref "R11") (pin "1") (pinfunction "1_1") (pintype "passive"))
      (node (ref "R5") (pin "2") (pinfunction "2_2") (pintype "passive"))
      (node (ref "X0") (pin "2") (pinfunction "5V_2") (pintype "power_in"))
      (node (ref "X0") (pin "4") (pinfunction "5V_4") (pintype "power_in"))
    )
    (net (code "41") (name "Net-(IC6-BST)") (class "Default")
      (node (ref "C8") (pin "1") (pinfunction "1_1") (pintype "passive"))
      (node (ref "IC6") (pin "6") (pinfunction "BST_6") (pintype "input"))
    )
    (net (code "42") (name "Net-(IC6-FB)") (class "Default")
      (node (ref "IC6") (pin "4") (pinfunction "FB_4") (pintype "input"))
      (node (ref "R10") (pin "2") (pinfunction "2_2") (pintype "passive"))
      (node (ref "R11") (pin "2") (pinfunction "2_2") (pintype "passive"))
    )
    (net (code "43") (name "Net-(IC6-SW)") (class "Default")
      (node (ref "C8") (pin "2") (pinfunction "2_2") (pintype "passive"))
      (node (ref "IC6") (pin "2") (pinfunction "SW_2") (pintype "passive"))
      (node (ref "L4.7") (pin "P$1") (pinfunction "1_P$1") (pintype "passive"))
    )
    (net (code "44") (name "Net-(JP2-Pad1)") (class "Default")
      (node (ref "JP2") (pin "1") (pinfunction "1_1") (pintype "passive"))
      (node (ref "R22") (pin "1") (pinfunction "1_1") (pintype "passive"))
    )
    (net (code "45") (name "Net-(JP3-Pad1)") (class "Default")
      (node (ref "JP3") (pin "1") (pinfunction "1_1") (pintype "passive"))
      (node (ref "R23") (pin "1") (pinfunction "1_1") (pintype "passive"))
    )
    (net (code "46") (name "Net-(LED1-PadC)") (class "Default")
      (node (ref "LED1") (pin "C") (pinfunction "C_C") (pintype "passive"))
      (node (ref "R24") (pin "2") (pinfunction "2_2") (pintype "passive"))
    )
    (net (code "47") (name "Net-(LED2-PadC)") (class "Default")
      (node (ref "LED2") (pin "C") (pinfunction "C_C") (pintype "passive"))
      (node (ref "R18") (pin "2") (pinfunction "2_2") (pintype "passive"))
    )
    (net (code "48") (name "Net-(LED3-PadC)") (class "Default")
      (node (ref "LED3") (pin "C") (pinfunction "C_C") (pintype "passive"))
      (node (ref "R21") (pin "2") (pinfunction "2_2") (pintype "passive"))
    )
    (net (code "49") (name "Net-(LED4-PadC)") (class "Default")
      (node (ref "LED4") (pin "C") (pinfunction "C_C") (pintype "passive"))
      (node (ref "R27") (pin "2") (pinfunction "2_2") (pintype "passive"))
    )
    (net (code "50") (name "Net-(Q1-D)") (class "Default")
      (node (ref "D2") (pin "A") (pinfunction "A_A") (pintype "passive"))
      (node (ref "K1") (pin "1") (pinfunction "1_1") (pintype "passive"))
      (node (ref "Q1") (pin "3") (pinfunction "D_3") (pintype "passive"))
      (node (ref "R24") (pin "1") (pinfunction "1_1") (pintype "passive"))
    )
    (net (code "51") (name "Net-(Q1-G)") (class "Default")
      (node (ref "Q1") (pin "1") (pinfunction "G_1") (pintype "passive"))
      (node (ref "R9") (pin "1") (pinfunction "1_1") (pintype "passive"))
    )
    (net (code "52") (name "Net-(Q2-D)") (class "Default")
      (node (ref "D1") (pin "A") (pinfunction "A_A") (pintype "passive"))
      (node (ref "K2") (pin "1") (pinfunction "1_1") (pintype "passive"))
      (node (ref "Q2") (pin "3") (pinfunction "D_3") (pintype "passive"))
      (node (ref "R18") (pin "1") (pinfunction "1_1") (pintype "passive"))
    )
    (net (code "53") (name "Net-(Q2-G)") (class "Default")
      (node (ref "Q2") (pin "1") (pinfunction "G_1") (pintype "passive"))
      (node (ref "R16") (pin "1") (pinfunction "1_1") (pintype "passive"))
    )
    (net (code "54") (name "Net-(Q3-D)") (class "Default")
      (node (ref "D3") (pin "A") (pinfunction "A_A") (pintype "passive"))
      (node (ref "K3") (pin "1") (pinfunction "1_1") (pintype "passive"))
      (node (ref "Q3") (pin "3") (pinfunction "D_3") (pintype "passive"))
      (node (ref "R21") (pin "1") (pinfunction "1_1") (pintype "passive"))
    )
    (net (code "55") (name "Net-(Q3-G)") (class "Default")
      (node (ref "Q3") (pin "1") (pinfunction "G_1") (pintype "passive"))
      (node (ref "R19") (pin "1") (pinfunction "1_1") (pintype "passive"))
    )
    (net (code "56") (name "Net-(Q4-D)") (class "Default")
      (node (ref "D4") (pin "A") (pinfunction "A_A") (pintype "passive"))
      (node (ref "K4") (pin "1") (pinfunction "1_1") (pintype "passive"))
      (node (ref "Q4") (pin "3") (pinfunction "D_3") (pintype "passive"))
      (node (ref "R27") (pin "1") (pinfunction "1_1") (pintype "passive"))
    )
    (net (code "57") (name "Net-(Q4-G)") (class "Default")
      (node (ref "Q4") (pin "1") (pinfunction "G_1") (pintype "passive"))
      (node (ref "R25") (pin "1") (pinfunction "1_1") (pintype "passive"))
    )
    (net (code "58") (name "Net-(X0-UART1_RX{slash}PG07)") (class "Default")
      (node (ref "R1") (pin "2") (pinfunction "2_2") (pintype "passive"))
      (node (ref "R3") (pin "2") (pinfunction "2_2") (pintype "passive"))
      (node (ref "X0") (pin "10") (pinfunction "UART1_RX/PG07_10") (pintype "bidirectional"))
    )
    (net (code "59") (name "Net-(X0-UART1_TX{slash}PG06)") (class "Default")
      (node (ref "R2") (pin "2") (pinfunction "2_2") (pintype "passive"))
      (node (ref "R4") (pin "2") (pinfunction "2_2") (pintype "passive"))
      (node (ref "X0") (pin "8") (pinfunction "UART1_TX/PG06_8") (pintype "bidirectional"))
    )
    (net (code "60") (name "Net-(X1A-KL)") (class "Default")
      (node (ref "K1") (pin "O") (pinfunction "O_O") (pintype "passive"))
      (node (ref "X1") (pin "1") (pinfunction "KL_1") (pintype "passive"))
    )
    (net (code "61") (name "Net-(X1B-KL)") (class "Default")
      (node (ref "K1") (pin "P") (pinfunction "P_P") (pintype "passive"))
      (node (ref "X1") (pin "2") (pinfunction "KL_2") (pintype "passive"))
    )
    (net (code "62") (name "Net-(X1C-KL)") (class "Default")
      (node (ref "K1") (pin "S") (pinfunction "S_S") (pintype "passive"))
      (node (ref "X1") (pin "3") (pinfunction "KL_3") (pintype "passive"))
    )
    (net (code "63") (name "Net-(X2A-KL)") (class "Default")
      (node (ref "K2") (pin "O") (pinfunction "O_O") (pintype "passive"))
      (node (ref "X2") (pin "1") (pinfunction "KL_1") (pintype "passive"))
    )
    (net (code "64") (name "Net-(X2B-KL)") (class "Default")
      (node (ref "K2") (pin "P") (pinfunction "P_P") (pintype "passive"))
      (node (ref "X2") (pin "2") (pinfunction "KL_2") (pintype "passive"))
    )
    (net (code "65") (name "Net-(X2C-KL)") (class "Default")
      (node (ref "K2") (pin "S") (pinfunction "S_S") (pintype "passive"))
      (node (ref "X2") (pin "3") (pinfunction "KL_3") (pintype "passive"))
    )
    (net (code "66") (name "Net-(X3A-KL)") (class "Default")
      (node (ref "K3") (pin "O") (pinfunction "O_O") (pintype "passive"))
      (node (ref "X3") (pin "1") (pinfunction "KL_1") (pintype "passive"))
    )
    (net (code "67") (name "Net-(X3B-KL)") (class "Default")
      (node (ref "K3") (pin "P") (pinfunction "P_P") (pintype "passive"))
      (node (ref "X3") (pin "2") (pinfunction "KL_2") (pintype "passive"))
    )
    (net (code "68") (name "Net-(X3C-KL)") (class "Default")
      (node (ref "K3") (pin "S") (pinfunction "S_S") (pintype "passive"))
      (node (ref "X3") (pin "3") (pinfunction "KL_3") (pintype "passive"))
    )
    (net (code "69") (name "Net-(X4A-KL)") (class "Default")
      (node (ref "K4") (pin "O") (pinfunction "O_O") (pintype "passive"))
      (node (ref "X4") (pin "1") (pinfunction "KL_1") (pintype "passive"))
    )
    (net (code "70") (name "Net-(X4B-KL)") (class "Default")
      (node (ref "K4") (pin "P") (pinfunction "P_P") (pintype "passive"))
      (node (ref "X4") (pin "2") (pinfunction "KL_2") (pintype "passive"))
    )
    (net (code "71") (name "Net-(X4C-KL)") (class "Default")
      (node (ref "K4") (pin "S") (pinfunction "S_S") (pintype "passive"))
      (node (ref "X4") (pin "3") (pinfunction "KL_3") (pintype "passive"))
    )
    (net (code "72") (name "VDD") (class "Default")
      (node (ref "1W-1") (pin "1") (pinfunction "K_1") (pintype "passive"))
      (node (ref "1W-2") (pin "1") (pinfunction "K_1") (pintype "passive"))
      (node (ref "C6") (pin "1") (pinfunction "1_1") (pintype "passive"))
      (node (ref "C7") (pin "1") (pinfunction "1_1") (pintype "passive"))
      (node (ref "D7") (pin "C") (pinfunction "C_C") (pintype "passive"))
      (node (ref "D8") (pin "2") (pinfunction "C2_2") (pintype "passive"))
      (node (ref "D9") (pin "2") (pinfunction "C2_2") (pintype "passive"))
      (node (ref "IC3") (pin "7") (pinfunction "AD1_7") (pintype "input"))
      (node (ref "IC5") (pin "2") (pinfunction "VOUT_2") (pintype "passive"))
      (node (ref "Q5") (pin "2") (pinfunction "S_2") (pintype "passive"))
      (node (ref "Q6") (pin "2") (pinfunction "S_2") (pintype "passive"))
      (node (ref "R31") (pin "2") (pinfunction "2_2") (pintype "passive"))
    )
    (net (code "73") (name "unconnected-(IC1-PC3(ADC3{slash}PCINT11)-Pad26)") (class "Default")
      (node (ref "IC1") (pin "26") (pinfunction "PC3(ADC3/PCINT11)_26") (pintype "bidirectional"))
    )
    (net (code "74") (name "unconnected-(IC1-PD3(INT1{slash}OC2B{slash}PCINT19)-Pad1)") (class "Default")
      (node (ref "IC1") (pin "1") (pinfunction "PD3(INT1/OC2B/PCINT19)_1") (pintype "bidirectional"))
    )
    (net (code "75") (name "unconnected-(IC1-PD4(T0{slash}XCK{slash}PCINT20)-Pad2)") (class "Default")
      (node (ref "IC1") (pin "2") (pinfunction "PD4(T0/XCK/PCINT20)_2") (pintype "bidirectional"))
    )
    (net (code "76") (name "unconnected-(X0-PA13{slash}SPI1_CS-Pad24)") (class "Default")
      (node (ref "X0") (pin "24") (pinfunction "PA13/SPI1_CS_24") (pintype "bidirectional"))
    )
    (net (code "77") (name "unconnected-(X0-PA14{slash}SPI1_CLK-Pad23)") (class "Default")
      (node (ref "X0") (pin "23") (pinfunction "PA14/SPI1_CLK_23") (pintype "bidirectional"))
    )
    (net (code "78") (name "unconnected-(X0-PA15{slash}SPI1_MOSI-Pad19)") (class "Default")
      (node (ref "X0") (pin "19") (pinfunction "PA15/SPI1_MOSI_19") (pintype "bidirectional"))
    )
    (net (code "79") (name "unconnected-(X0-PA16{slash}SPI1_MISO-Pad21)") (class "Default")
      (node (ref "X0") (pin "21") (pinfunction "PA16/SPI1_MISO_21") (pintype "bidirectional"))
    )
    (net (code "80") (name "unconnected-(X0-PA18{slash}TWI1_SCL-Pad18)") (class "Default")
      (node (ref "X0") (pin "18") (pinfunction "PA18/TWI1_SCL_18") (pintype "bidirectional"))
    )
    (net (code "81") (name "unconnected-(X0-PA19{slash}TWI1_SDA-Pad16)") (class "Default")
      (node (ref "X0") (pin "16") (pinfunction "PA19/TWI1_SDA_16") (pintype "bidirectional"))
    )
    (net (code "82") (name "unconnected-(X0-PWM1{slash}PA06-Pad7)") (class "Default")
      (node (ref "X0") (pin "7") (pinfunction "PWM1/PA06_7") (pintype "bidirectional"))
    )
    (net (code "83") (name "unconnected-(X0-SIM_CLK{slash}PA_EINT7{slash}PA07-Pad12)") (class "Default")
      (node (ref "X0") (pin "12") (pinfunction "SIM_CLK/PA_EINT7/PA07_12") (pintype "bidirectional"))
    )
    (net (code "84") (name "unconnected-(X0-SIM_DET{slash}PA_EINT10{slash}PA10-Pad26)") (class "Default")
      (node (ref "X0") (pin "26") (pinfunction "SIM_DET/PA_EINT10/PA10_26") (pintype "bidirectional"))
    )
    (net (code "85") (name "unconnected-(X0-UART2_CTS{slash}PA03-Pad15)") (class "Default")
      (node (ref "X0") (pin "15") (pinfunction "UART2_CTS/PA03_15") (pintype "bidirectional"))
    )
    (net (code "86") (name "unconnected-(X0-UART2_RTS{slash}PA02-Pad22)") (class "Default")
      (node (ref "X0") (pin "22") (pinfunction "UART2_RTS/PA02_22") (pintype "bidirectional"))
    )
    (net (code "87") (name "unconnected-(X0-UART2_RX{slash}PA01-Pad11)") (class "Default")
      (node (ref "X0") (pin "11") (pinfunction "UART2_RX/PA01_11") (pintype "bidirectional"))
    )
    (net (code "88") (name "unconnected-(X0-UART2_TX{slash}PA00-Pad13)") (class "Default")
      (node (ref "X0") (pin "13") (pinfunction "UART2_TX/PA00_13") (pintype "bidirectional"))
    )
  )
)
